# ESP32-WROOM-32D_Module.net
KiCad netlist of a schematic drawn in Altium Designer
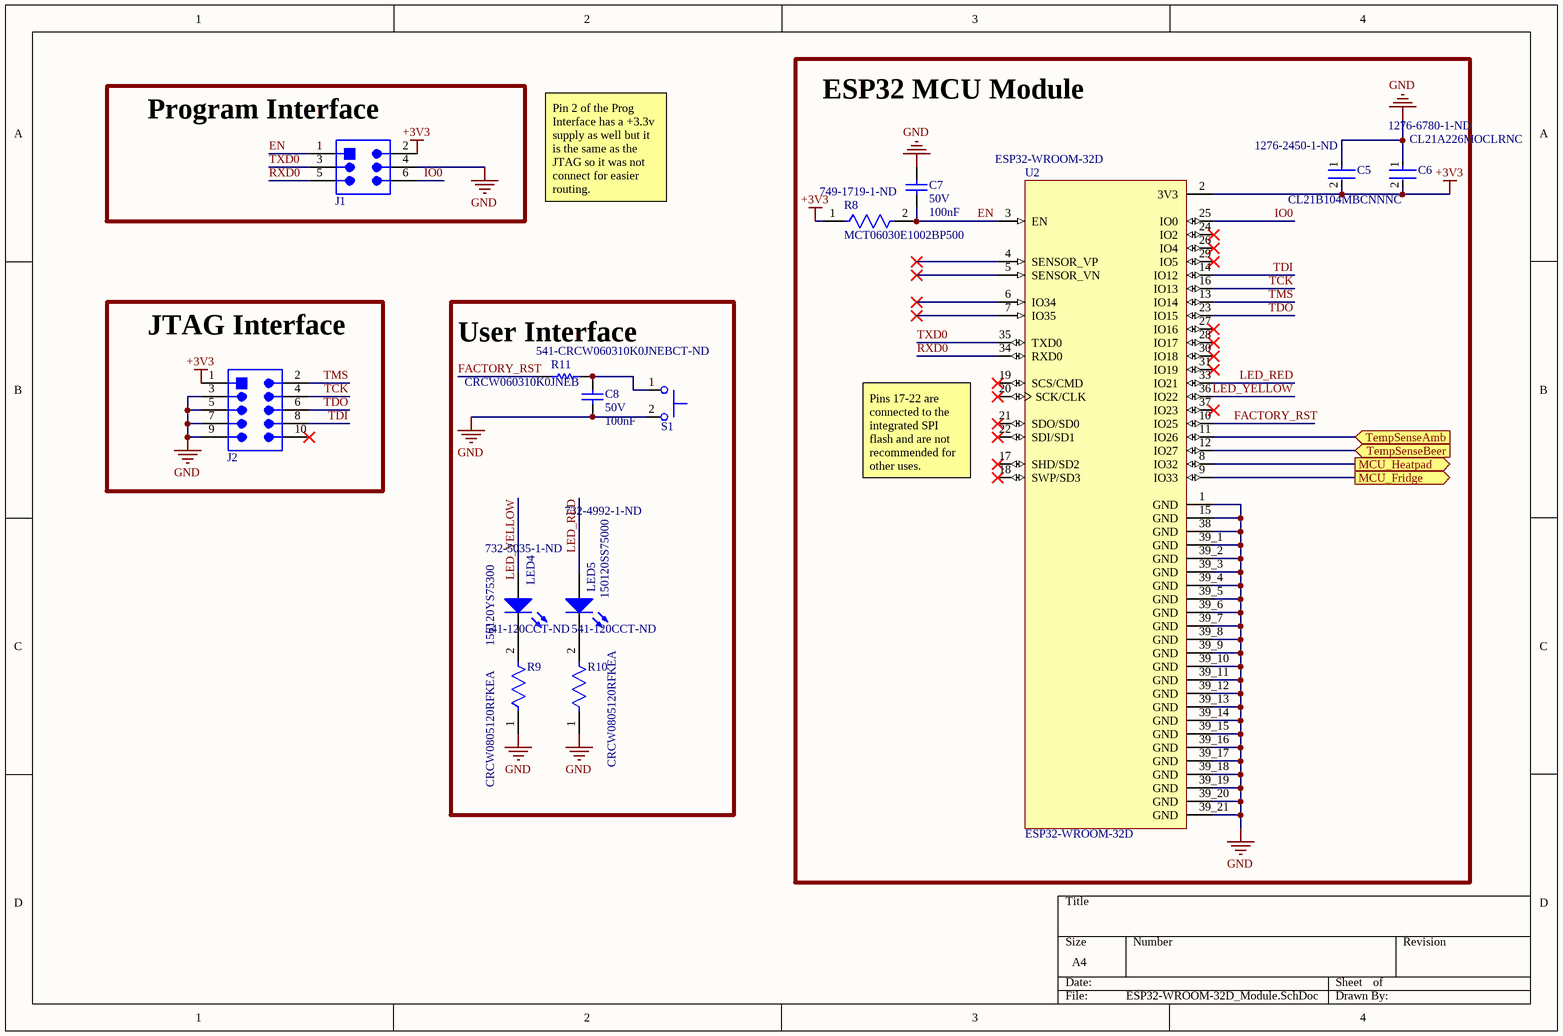
[diagram p0: ESP32-WROOM-32D_Module.SchDoc]

(export (version "E")
  (design (tool "Eeschema 10.0.6"))
  (components
    (comp (ref "C5")
      (value "CL21B104MBCNNNC")
      (footprint "FP-CL21-IPC_B")
      (description "CL21 Series 0805 100nF 50V ±20% Tolerance X7R Multilayer Ceramic Chip Capacitor")
      (fields
        (field (name "VOLTAGE") "50V")
        (field (name "TOLERANCE") "20%")
        (field (name "SUPPLIER PART NUMBER 1") "1276-2450-1-ND")
      )
      (libsource (lib "Altium Content Vault") (part "b4654b650e69147ec39a6b967a45e02"))
    )
    (comp (ref "C6")
      (value "CL21A226MOCLRNC")
      (footprint "FP-CL21-IPC_C")
      (description "CL21 Series 0805 22uF 16V ±20% Tolerance X5R Multilayer Ceramic Chip Capacitor")
      (fields
        (field (name "TOLERANCE") "20%")
        (field (name "SUPPLIER PART NUMBER 1") "1276-6780-1-ND")
        (field (name "MANUFACTURER") "Samsung")
      )
      (libsource (lib "Altium Content Vault") (part "b4654b650e69147ec39a6b967a45e02"))
    )
    (comp (ref "C7")
      (value "Cap 0.1uF/50V 0805 X7R (CL21B104MBCNNNC)")
      (footprint "C0805")
      (description "Cap Ceramic 0.1uF 50V X7R 20% SMD 0805 125C Paper T/R")
      (fields
        (field (name "TOLERANCE") "20%")
        (field (name "VOLTAGE") "50V")
        (field (name "VOLTAGE RATING (DC)") "50V")
        (field (name "CAPACITANCE") "100nF")
      )
      (libsource (lib "3-0006_Schlib") (part "Cap 0.1uF/50V 0805 X7R (CL21B104MBCNNNC)"))
    )
    (comp (ref "C8")
      (value "Cap 0.1uF/50V 0805 X7R (CL21B104MBCNNNC)")
      (footprint "C0805")
      (description "Cap Ceramic 0.1uF 50V X7R 20% SMD 0805 125C Paper T/R")
      (fields
        (field (name "TOLERANCE") "20%")
        (field (name "VOLTAGE") "50V")
        (field (name "VOLTAGE RATING (DC)") "50V")
        (field (name "CAPACITANCE") "100nF")
      )
      (libsource (lib "3-0006_Schlib") (part "Cap 0.1uF/50V 0805 X7R (CL21B104MBCNNNC)"))
    )
    (comp (ref "J1")
      (value "6Pos 1.27mm Unkeyed (20021111-00006T4LF)")
      (footprint "6Pos_1.27_Keyed")
      (description "CONN HEADER 6POS UNSHD VERT T/H")
      (fields
        (field (name "MANUFACTURER") "Amphenol FCI")
        (field (name "MANUFACTURER PART NUMBER") "20021111-00006T4LF")
      )
      (libsource (lib "BrewController") (part "6Pos 1.27mm Unkeyed (20021111-00006T4LF)"))
    )
    (comp (ref "J2")
      (value "10Pos 1.27mm Keyed (3220-10-0100-00)")
      (footprint "10pos_1.27_Keyed")
      (description "CONN HEADER VERT 10POS 1.27MM")
      (fields
        (field (name "MANUFACTURER") "CNC Tech")
        (field (name "MANUFACTURER PART NUMBER") "3220-10-0100-00")
      )
      (libsource (lib "BrewController") (part "10Pos 1.27mm Keyed (3220-10-0100-00)"))
    )
    (comp (ref "LED4")
      (value "156120YS75300")
      (footprint "1206  CYLINDRICAL- Reverse Use")
      (description "SMD mono-color reverse mount waterclear Chip LED, WL-SMRW, Yellow")
      (fields
        (field (name "MANUFACTURER") "Wuerth Elektronik")
        (field (name "SUPPLIER PART NUMBER 1") "732-5035-1-ND")
      )
      (libsource (lib "Altium Content Vault") (part "WE-LED_K1A2-2"))
    )
    (comp (ref "LED5")
      (value "150120SS75000")
      (footprint "1206_A")
      (description "SMD mono-color Chip LED, WL-SMCW, Super Red")
      (fields
        (field (name "MANUFACTURER") "Wuerth Elektronik")
        (field (name "SUPPLIER PART NUMBER 1") "732-4992-1-ND")
      )
      (libsource (lib "Altium Content Vault") (part "WE-LED_K1A2-2"))
    )
    (comp (ref "R8")
      (value "MCT06030E1002BP500")
      (footprint "FP-MCT0603-MFG")
      (description "RES SMD 100 OHM 1% 1/8W 0603")
      (fields
        (field (name "TOLERANCE") "0.1%")
        (field (name "SUPPLIER PART NUMBER 1") "749-1719-1-ND")
        (field (name "MANUFACTURER") "Vishay BCcomponents")
      )
      (libsource (lib "Altium Content Vault") (part "1029c3af85768c4190bb7ad29bc67b5"))
    )
    (comp (ref "R9")
      (value "CRCW0805120RFKEA")
      (footprint "FP-CRCW0805-e3-IPC_C")
      (description "RES Thick Film, 120Ω, 1%, 0.125W, 100ppm/°C, 0805")
      (fields
        (field (name "TOLERANCE") "1%")
        (field (name "SUPPLIER PART NUMBER 1") "541-120CCT-ND")
        (field (name "MANUFACTURER") "Vishay")
      )
      (libsource (lib "Altium Content Vault") (part "1029c3af85768c4190bb7ad29bc67b5"))
    )
    (comp (ref "R10")
      (value "CRCW0805120RFKEA")
      (footprint "FP-CRCW0805-e3-IPC_C")
      (description "RES Thick Film, 120Ω, 1%, 0.125W, 100ppm/°C, 0805")
      (fields
        (field (name "TOLERANCE") "1%")
        (field (name "SUPPLIER PART NUMBER 1") "541-120CCT-ND")
        (field (name "MANUFACTURER") "Vishay")
      )
      (libsource (lib "Altium Content Vault") (part "1029c3af85768c4190bb7ad29bc67b5"))
    )
    (comp (ref "R11")
      (value "CRCW060310K0JNEB")
      (footprint "RESC1609X50X30LL10T20")
      (description "Res Thick Film 0603 10K Ohm 5% 0.1W(1/10W) ±200ppm/C Molded SMD Automotive Paper T/R")
      (fields
        (field (name "MANUFACTURER") "Vishay Dale")
        (field (name "SUPPLIER PART NUMBER 1") "541-CRCW060310K0JNEBCT-ND")
        (field (name "TOLERANCE") "5%")
      )
      (libsource (lib "Altium Content Vault") (part "RES"))
    )
    (comp (ref "S1")
      (value "Right Angle SMT Edge Switch")
      (footprint "TL4110 Edge Connector")
      (description "RIGHT ANGLE SMT TACT SWITCH 2.0M")
      (fields
        (field (name "MANUFACTURER") "E-Switch")
        (field (name "MANUFACTURER PART NUMBER") "TL4110AF160Q")
      )
      (libsource (lib "BrewController") (part "Right Angle SMT Edge Switch"))
    )
    (comp (ref "U2")
      (value "ESP32-WROOM-32D")
      (footprint "*MODULE_ESP32-WROOM-32D_ESP32-WROOM-32D(Primary)")
      (description "Wi-Fi/BT BLE Module ESP32-D0WD, SPI Flash, UART, P")
      (fields
        (field (name "SUPPLIER PART NUMBER 2") "ESP32-WROOM-32D")
        (field (name "MANUFACTURER") "Espressif Systems")
      )
      (libsource (lib "3-0006_Schlib") (part "ESP32-WROOM-32D"))
    )
  )
  (nets
    (net (code "1") (name "+3V3") (class "Default")
      (node (ref "C5") (pin "2") (pinfunction "2_2") (pintype "passive"))
      (node (ref "C6") (pin "2") (pinfunction "2_2") (pintype "passive"))
      (node (ref "J1") (pin "2") (pinfunction "2_2") (pintype "passive"))
      (node (ref "J2") (pin "1") (pinfunction "1_1") (pintype "passive"))
      (node (ref "R8") (pin "1") (pinfunction "1_1") (pintype "passive"))
      (node (ref "U2") (pin "2") (pinfunction "3V3_2") (pintype "power_in"))
    )
    (net (code "2") (name "/EN") (class "Default")
      (node (ref "C7") (pin "1") (pinfunction "1_1") (pintype "passive"))
      (node (ref "J1") (pin "1") (pinfunction "1_1") (pintype "passive"))
      (node (ref "R8") (pin "2") (pinfunction "2_2") (pintype "passive"))
      (node (ref "U2") (pin "3") (pinfunction "EN_3") (pintype "input"))
    )
    (net (code "3") (name "/FACTORY_RST") (class "Default")
      (node (ref "R11") (pin "1") (pinfunction "1_1") (pintype "passive"))
      (node (ref "U2") (pin "10") (pinfunction "IO25_10") (pintype "bidirectional"))
    )
    (net (code "4") (name "/IO0") (class "Default")
      (node (ref "J1") (pin "6") (pinfunction "6_6") (pintype "passive"))
      (node (ref "U2") (pin "25") (pinfunction "IO0_25") (pintype "bidirectional"))
    )
    (net (code "5") (name "/LED_RED") (class "Default")
      (node (ref "LED5") (pin "2") (pinfunction "A_2") (pintype "passive"))
      (node (ref "U2") (pin "33") (pinfunction "IO21_33") (pintype "bidirectional"))
    )
    (net (code "6") (name "/LED_YELLOW") (class "Default")
      (node (ref "LED4") (pin "2") (pinfunction "A_2") (pintype "passive"))
      (node (ref "U2") (pin "36") (pinfunction "IO22_36") (pintype "bidirectional"))
    )
    (net (code "7") (name "/MCU_Fridge") (class "Default")
      (node (ref "U2") (pin "9") (pinfunction "IO33_9") (pintype "bidirectional"))
    )
    (net (code "8") (name "/MCU_Heatpad") (class "Default")
      (node (ref "U2") (pin "8") (pinfunction "IO32_8") (pintype "bidirectional"))
    )
    (net (code "9") (name "/RXD0") (class "Default")
      (node (ref "J1") (pin "5") (pinfunction "5_5") (pintype "passive"))
      (node (ref "U2") (pin "34") (pinfunction "RXD0_34") (pintype "bidirectional"))
    )
    (net (code "10") (name "/TCK") (class "Default")
      (node (ref "J2") (pin "4") (pinfunction "4_4") (pintype "passive"))
      (node (ref "U2") (pin "16") (pinfunction "IO13_16") (pintype "bidirectional"))
    )
    (net (code "11") (name "/TDI") (class "Default")
      (node (ref "J2") (pin "8") (pinfunction "8_8") (pintype "passive"))
      (node (ref "U2") (pin "14") (pinfunction "IO12_14") (pintype "bidirectional"))
    )
    (net (code "12") (name "/TDO") (class "Default")
      (node (ref "J2") (pin "6") (pinfunction "6_6") (pintype "passive"))
      (node (ref "U2") (pin "23") (pinfunction "IO15_23") (pintype "bidirectional"))
    )
    (net (code "13") (name "/TMS") (class "Default")
      (node (ref "J2") (pin "2") (pinfunction "2_2") (pintype "passive"))
      (node (ref "U2") (pin "13") (pinfunction "IO14_13") (pintype "bidirectional"))
    )
    (net (code "14") (name "/TXD0") (class "Default")
      (node (ref "J1") (pin "3") (pinfunction "3_3") (pintype "passive"))
      (node (ref "U2") (pin "35") (pinfunction "TXD0_35") (pintype "bidirectional"))
    )
    (net (code "15") (name "/TempSenseAmb") (class "Default")
      (node (ref "U2") (pin "11") (pinfunction "IO26_11") (pintype "bidirectional"))
    )
    (net (code "16") (name "/TempSenseBeer") (class "Default")
      (node (ref "U2") (pin "12") (pinfunction "IO27_12") (pintype "bidirectional"))
    )
    (net (code "17") (name "GND") (class "Default")
      (node (ref "C5") (pin "1") (pinfunction "1_1") (pintype "passive"))
      (node (ref "C6") (pin "1") (pinfunction "1_1") (pintype "passive"))
      (node (ref "C7") (pin "2") (pinfunction "2_2") (pintype "passive"))
      (node (ref "C8") (pin "1") (pinfunction "1_1") (pintype "passive"))
      (node (ref "J1") (pin "4") (pinfunction "4_4") (pintype "passive"))
      (node (ref "J2") (pin "3") (pinfunction "3_3") (pintype "passive"))
      (node (ref "J2") (pin "5") (pinfunction "5_5") (pintype "passive"))
      (node (ref "J2") (pin "7") (pinfunction "7_7") (pintype "passive"))
      (node (ref "J2") (pin "9") (pinfunction "9_9") (pintype "passive"))
      (node (ref "R10") (pin "1") (pinfunction "1_1") (pintype "passive"))
      (node (ref "R9") (pin "1") (pinfunction "1_1") (pintype "passive"))
      (node (ref "S1") (pin "2") (pinfunction "2_2") (pintype "passive"))
      (node (ref "U2") (pin "1") (pinfunction "GND_1") (pintype "power_in"))
      (node (ref "U2") (pin "15") (pinfunction "GND_15") (pintype "power_in"))
      (node (ref "U2") (pin "38") (pinfunction "GND_38") (pintype "power_in"))
      (node (ref "U2") (pin "39_1") (pinfunction "GND_39_1") (pintype "power_in"))
      (node (ref "U2") (pin "39_10") (pinfunction "GND_39_10") (pintype "power_in"))
      (node (ref "U2") (pin "39_11") (pinfunction "GND_39_11") (pintype "power_in"))
      (node (ref "U2") (pin "39_12") (pinfunction "GND_39_12") (pintype "power_in"))
      (node (ref "U2") (pin "39_13") (pinfunction "GND_39_13") (pintype "power_in"))
      (node (ref "U2") (pin "39_14") (pinfunction "GND_39_14") (pintype "power_in"))
      (node (ref "U2") (pin "39_15") (pinfunction "GND_39_15") (pintype "power_in"))
      (node (ref "U2") (pin "39_16") (pinfunction "GND_39_16") (pintype "power_in"))
      (node (ref "U2") (pin "39_17") (pinfunction "GND_39_17") (pintype "power_in"))
      (node (ref "U2") (pin "39_18") (pinfunction "GND_39_18") (pintype "power_in"))
      (node (ref "U2") (pin "39_19") (pinfunction "GND_39_19") (pintype "power_in"))
      (node (ref "U2") (pin "39_2") (pinfunction "GND_39_2") (pintype "power_in"))
      (node (ref "U2") (pin "39_20") (pinfunction "GND_39_20") (pintype "power_in"))
      (node (ref "U2") (pin "39_21") (pinfunction "GND_39_21") (pintype "power_in"))
      (node (ref "U2") (pin "39_3") (pinfunction "GND_39_3") (pintype "power_in"))
      (node (ref "U2") (pin "39_4") (pinfunction "GND_39_4") (pintype "power_in"))
      (node (ref "U2") (pin "39_5") (pinfunction "GND_39_5") (pintype "power_in"))
      (node (ref "U2") (pin "39_6") (pinfunction "GND_39_6") (pintype "power_in"))
      (node (ref "U2") (pin "39_7") (pinfunction "GND_39_7") (pintype "power_in"))
      (node (ref "U2") (pin "39_8") (pinfunction "GND_39_8") (pintype "power_in"))
      (node (ref "U2") (pin "39_9") (pinfunction "GND_39_9") (pintype "power_in"))
    )
    (net (code "18") (name "Net-(C8-Pad2)") (class "Default")
      (node (ref "C8") (pin "2") (pinfunction "2_2") (pintype "passive"))
      (node (ref "R11") (pin "2") (pinfunction "2_2") (pintype "passive"))
      (node (ref "S1") (pin "1") (pinfunction "1_1") (pintype "passive"))
    )
    (net (code "19") (name "Net-(LED4-K)") (class "Default")
      (node (ref "LED4") (pin "1") (pinfunction "K_1") (pintype "passive"))
      (node (ref "R9") (pin "2") (pinfunction "2_2") (pintype "passive"))
    )
    (net (code "20") (name "Net-(LED5-K)") (class "Default")
      (node (ref "LED5") (pin "1") (pinfunction "K_1") (pintype "passive"))
      (node (ref "R10") (pin "2") (pinfunction "2_2") (pintype "passive"))
    )
    (net (code "21") (name "unconnected-(J2-Pad10)") (class "Default")
      (node (ref "J2") (pin "10") (pinfunction "10_10") (pintype "passive+no_connect"))
    )
    (net (code "22") (name "unconnected-(U2-IO2-Pad24)") (class "Default")
      (node (ref "U2") (pin "24") (pinfunction "IO2_24") (pintype "bidirectional+no_connect"))
    )
    (net (code "23") (name "unconnected-(U2-IO4-Pad26)") (class "Default")
      (node (ref "U2") (pin "26") (pinfunction "IO4_26") (pintype "bidirectional+no_connect"))
    )
    (net (code "24") (name "unconnected-(U2-IO5-Pad29)") (class "Default")
      (node (ref "U2") (pin "29") (pinfunction "IO5_29") (pintype "bidirectional+no_connect"))
    )
    (net (code "25") (name "unconnected-(U2-IO16-Pad27)") (class "Default")
      (node (ref "U2") (pin "27") (pinfunction "IO16_27") (pintype "bidirectional+no_connect"))
    )
    (net (code "26") (name "unconnected-(U2-IO17-Pad28)") (class "Default")
      (node (ref "U2") (pin "28") (pinfunction "IO17_28") (pintype "bidirectional+no_connect"))
    )
    (net (code "27") (name "unconnected-(U2-IO18-Pad30)") (class "Default")
      (node (ref "U2") (pin "30") (pinfunction "IO18_30") (pintype "bidirectional+no_connect"))
    )
    (net (code "28") (name "unconnected-(U2-IO19-Pad31)") (class "Default")
      (node (ref "U2") (pin "31") (pinfunction "IO19_31") (pintype "bidirectional+no_connect"))
    )
    (net (code "29") (name "unconnected-(U2-IO23-Pad37)") (class "Default")
      (node (ref "U2") (pin "37") (pinfunction "IO23_37") (pintype "bidirectional+no_connect"))
    )
    (net (code "30") (name "unconnected-(U2-IO34-Pad6)") (class "Default")
      (node (ref "U2") (pin "6") (pinfunction "IO34_6") (pintype "input+no_connect"))
    )
    (net (code "31") (name "unconnected-(U2-IO35-Pad7)") (class "Default")
      (node (ref "U2") (pin "7") (pinfunction "IO35_7") (pintype "input+no_connect"))
    )
    (net (code "32") (name "unconnected-(U2-SCK{slash}CLK-Pad20)") (class "Default")
      (node (ref "U2") (pin "20") (pinfunction "SCK/CLK_20") (pintype "bidirectional+no_connect"))
    )
    (net (code "33") (name "unconnected-(U2-SCS{slash}CMD-Pad19)") (class "Default")
      (node (ref "U2") (pin "19") (pinfunction "SCS/CMD_19") (pintype "bidirectional+no_connect"))
    )
    (net (code "34") (name "unconnected-(U2-SDI{slash}SD1-Pad22)") (class "Default")
      (node (ref "U2") (pin "22") (pinfunction "SDI/SD1_22") (pintype "bidirectional+no_connect"))
    )
    (net (code "35") (name "unconnected-(U2-SDO{slash}SD0-Pad21)") (class "Default")
      (node (ref "U2") (pin "21") (pinfunction "SDO/SD0_21") (pintype "bidirectional+no_connect"))
    )
    (net (code "36") (name "unconnected-(U2-SENSOR_VN-Pad5)") (class "Default")
      (node (ref "U2") (pin "5") (pinfunction "SENSOR_VN_5") (pintype "input+no_connect"))
    )
    (net (code "37") (name "unconnected-(U2-SENSOR_VP-Pad4)") (class "Default")
      (node (ref "U2") (pin "4") (pinfunction "SENSOR_VP_4") (pintype "input+no_connect"))
    )
    (net (code "38") (name "unconnected-(U2-SHD{slash}SD2-Pad17)") (class "Default")
      (node (ref "U2") (pin "17") (pinfunction "SHD/SD2_17") (pintype "bidirectional+no_connect"))
    )
    (net (code "39") (name "unconnected-(U2-SWP{slash}SD3-Pad18)") (class "Default")
      (node (ref "U2") (pin "18") (pinfunction "SWP/SD3_18") (pintype "bidirectional+no_connect"))
    )
  )
)
